# RFM96H.net
KiCad netlist of a schematic drawn in EAGLE
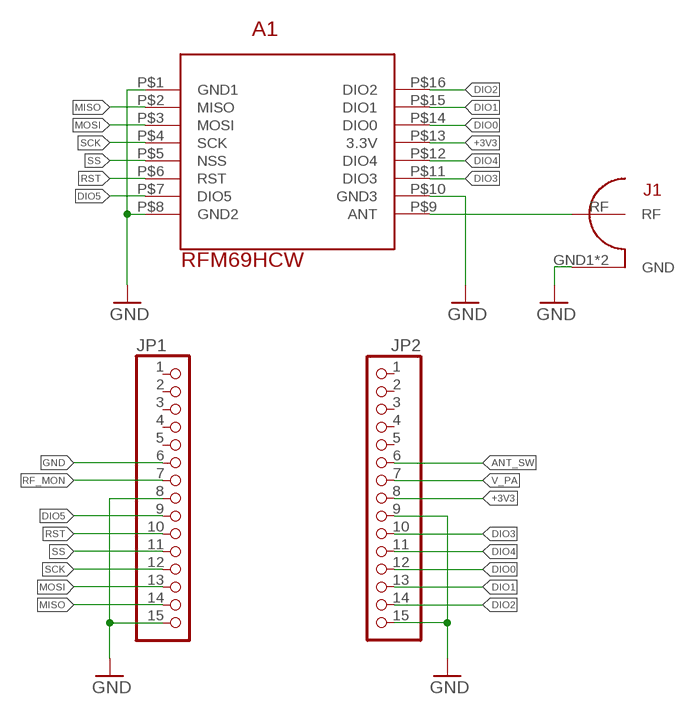
[diagram p0: schematic, sheet 1]

(export (version "E")
  (design (tool "Eeschema 10.0.6"))
  (components
    (comp (ref "A1")
      (value "RFM69HCW")
      (footprint "eagle-import:RFM69HCW")
      (fields (field (name "PARTNO") "1568-1394-ND"))
      (libsource (lib "eagle-import") (part "RFM69HCW"))
    )
    (comp (ref "J1")
      (value "CON-SMA-EDGE-S")
      (footprint "eagle-import:CON-SMA-EDGE-S")
      (fields (field (name "PARTNO") "CON-SMA-EDGE-S-ND"))
      (libsource (lib "eagle-import") (part "CON-SMA-EDGE-S"))
    )
    (comp (ref "JP1")
      (value "PINHD-1X15")
      (footprint "eagle-import:1X15")
      (libsource (lib "eagle-import") (part "PINHD-1X15"))
    )
    (comp (ref "JP2")
      (value "PINHD-1X15")
      (footprint "eagle-import:1X15")
      (libsource (lib "eagle-import") (part "PINHD-1X15"))
    )
  )
  (nets
    (net (code "1") (name "+3V3") (class "Default")
      (node (ref "A1") (pin "P$13") (pinfunction "3.3V_P$13") (pintype "bidirectional"))
      (node (ref "JP2") (pin "8") (pinfunction "8_8") (pintype "passive"))
    )
    (net (code "2") (name "ANT_SW") (class "Default")
      (node (ref "JP2") (pin "6") (pinfunction "6_6") (pintype "passive"))
    )
    (net (code "3") (name "DIO0") (class "Default")
      (node (ref "A1") (pin "P$14") (pinfunction "DIO0_P$14") (pintype "bidirectional"))
      (node (ref "JP2") (pin "12") (pinfunction "12_12") (pintype "passive"))
    )
    (net (code "4") (name "DIO1") (class "Default")
      (node (ref "A1") (pin "P$15") (pinfunction "DIO1_P$15") (pintype "bidirectional"))
      (node (ref "JP2") (pin "13") (pinfunction "13_13") (pintype "passive"))
    )
    (net (code "5") (name "DIO2") (class "Default")
      (node (ref "A1") (pin "P$16") (pinfunction "DIO2_P$16") (pintype "bidirectional"))
      (node (ref "JP2") (pin "14") (pinfunction "14_14") (pintype "passive"))
    )
    (net (code "6") (name "DIO3") (class "Default")
      (node (ref "A1") (pin "P$11") (pinfunction "DIO3_P$11") (pintype "bidirectional"))
      (node (ref "JP2") (pin "10") (pinfunction "10_10") (pintype "passive"))
    )
    (net (code "7") (name "DIO4") (class "Default")
      (node (ref "A1") (pin "P$12") (pinfunction "DIO4_P$12") (pintype "bidirectional"))
      (node (ref "JP2") (pin "11") (pinfunction "11_11") (pintype "passive"))
    )
    (net (code "8") (name "DIO5") (class "Default")
      (node (ref "A1") (pin "P$7") (pinfunction "DIO5_P$7") (pintype "bidirectional"))
      (node (ref "JP1") (pin "9") (pinfunction "9_9") (pintype "passive"))
    )
    (net (code "9") (name "GND") (class "Default")
      (node (ref "A1") (pin "P$1") (pinfunction "GND1_P$1") (pintype "bidirectional"))
      (node (ref "A1") (pin "P$10") (pinfunction "GND3_P$10") (pintype "bidirectional"))
      (node (ref "A1") (pin "P$8") (pinfunction "GND2_P$8") (pintype "bidirectional"))
      (node (ref "J1") (pin "GND1") (pinfunction "GND_GND1") (pintype "bidirectional"))
      (node (ref "J1") (pin "GND2") (pinfunction "GND_GND2") (pintype "bidirectional"))
      (node (ref "JP1") (pin "15") (pinfunction "15_15") (pintype "passive"))
      (node (ref "JP1") (pin "6") (pinfunction "6_6") (pintype "passive"))
      (node (ref "JP1") (pin "8") (pinfunction "8_8") (pintype "passive"))
      (node (ref "JP2") (pin "15") (pinfunction "15_15") (pintype "passive"))
      (node (ref "JP2") (pin "9") (pinfunction "9_9") (pintype "passive"))
    )
    (net (code "10") (name "MISO") (class "Default")
      (node (ref "A1") (pin "P$2") (pinfunction "MISO_P$2") (pintype "bidirectional"))
      (node (ref "JP1") (pin "14") (pinfunction "14_14") (pintype "passive"))
    )
    (net (code "11") (name "MOSI") (class "Default")
      (node (ref "A1") (pin "P$3") (pinfunction "MOSI_P$3") (pintype "bidirectional"))
      (node (ref "JP1") (pin "13") (pinfunction "13_13") (pintype "passive"))
    )
    (net (code "12") (name "Net-(A1-ANT)") (class "Default")
      (node (ref "A1") (pin "P$9") (pinfunction "ANT_P$9") (pintype "bidirectional"))
      (node (ref "J1") (pin "RF") (pinfunction "RF_RF") (pintype "bidirectional"))
    )
    (net (code "13") (name "RF_MON") (class "Default")
      (node (ref "JP1") (pin "7") (pinfunction "7_7") (pintype "passive"))
    )
    (net (code "14") (name "RST") (class "Default")
      (node (ref "A1") (pin "P$6") (pinfunction "RST_P$6") (pintype "bidirectional"))
      (node (ref "JP1") (pin "10") (pinfunction "10_10") (pintype "passive"))
    )
    (net (code "15") (name "SCK") (class "Default")
      (node (ref "A1") (pin "P$4") (pinfunction "SCK_P$4") (pintype "bidirectional"))
      (node (ref "JP1") (pin "12") (pinfunction "12_12") (pintype "passive"))
    )
    (net (code "16") (name "SS") (class "Default")
      (node (ref "A1") (pin "P$5") (pinfunction "NSS_P$5") (pintype "bidirectional"))
      (node (ref "JP1") (pin "11") (pinfunction "11_11") (pintype "passive"))
    )
    (net (code "17") (name "V_PA") (class "Default")
      (node (ref "JP2") (pin "7") (pinfunction "7_7") (pintype "passive"))
    )
    (net (code "18") (name "unconnected-(JP1-Pad1)") (class "Default")
      (node (ref "JP1") (pin "1") (pinfunction "1_1") (pintype "passive"))
    )
    (net (code "19") (name "unconnected-(JP1-Pad2)") (class "Default")
      (node (ref "JP1") (pin "2") (pinfunction "2_2") (pintype "passive"))
    )
    (net (code "20") (name "unconnected-(JP1-Pad3)") (class "Default")
      (node (ref "JP1") (pin "3") (pinfunction "3_3") (pintype "passive"))
    )
    (net (code "21") (name "unconnected-(JP1-Pad4)") (class "Default")
      (node (ref "JP1") (pin "4") (pinfunction "4_4") (pintype "passive"))
    )
    (net (code "22") (name "unconnected-(JP1-Pad5)") (class "Default")
      (node (ref "JP1") (pin "5") (pinfunction "5_5") (pintype "passive"))
    )
    (net (code "23") (name "unconnected-(JP2-Pad1)") (class "Default")
      (node (ref "JP2") (pin "1") (pinfunction "1_1") (pintype "passive"))
    )
    (net (code "24") (name "unconnected-(JP2-Pad2)") (class "Default")
      (node (ref "JP2") (pin "2") (pinfunction "2_2") (pintype "passive"))
    )
    (net (code "25") (name "unconnected-(JP2-Pad3)") (class "Default")
      (node (ref "JP2") (pin "3") (pinfunction "3_3") (pintype "passive"))
    )
    (net (code "26") (name "unconnected-(JP2-Pad4)") (class "Default")
      (node (ref "JP2") (pin "4") (pinfunction "4_4") (pintype "passive"))
    )
    (net (code "27") (name "unconnected-(JP2-Pad5)") (class "Default")
      (node (ref "JP2") (pin "5") (pinfunction "5_5") (pintype "passive"))
    )
  )
)
